# SCH_Genie-V1_2024-07-29.net
KiCad netlist of a schematic drawn in EasyEDA
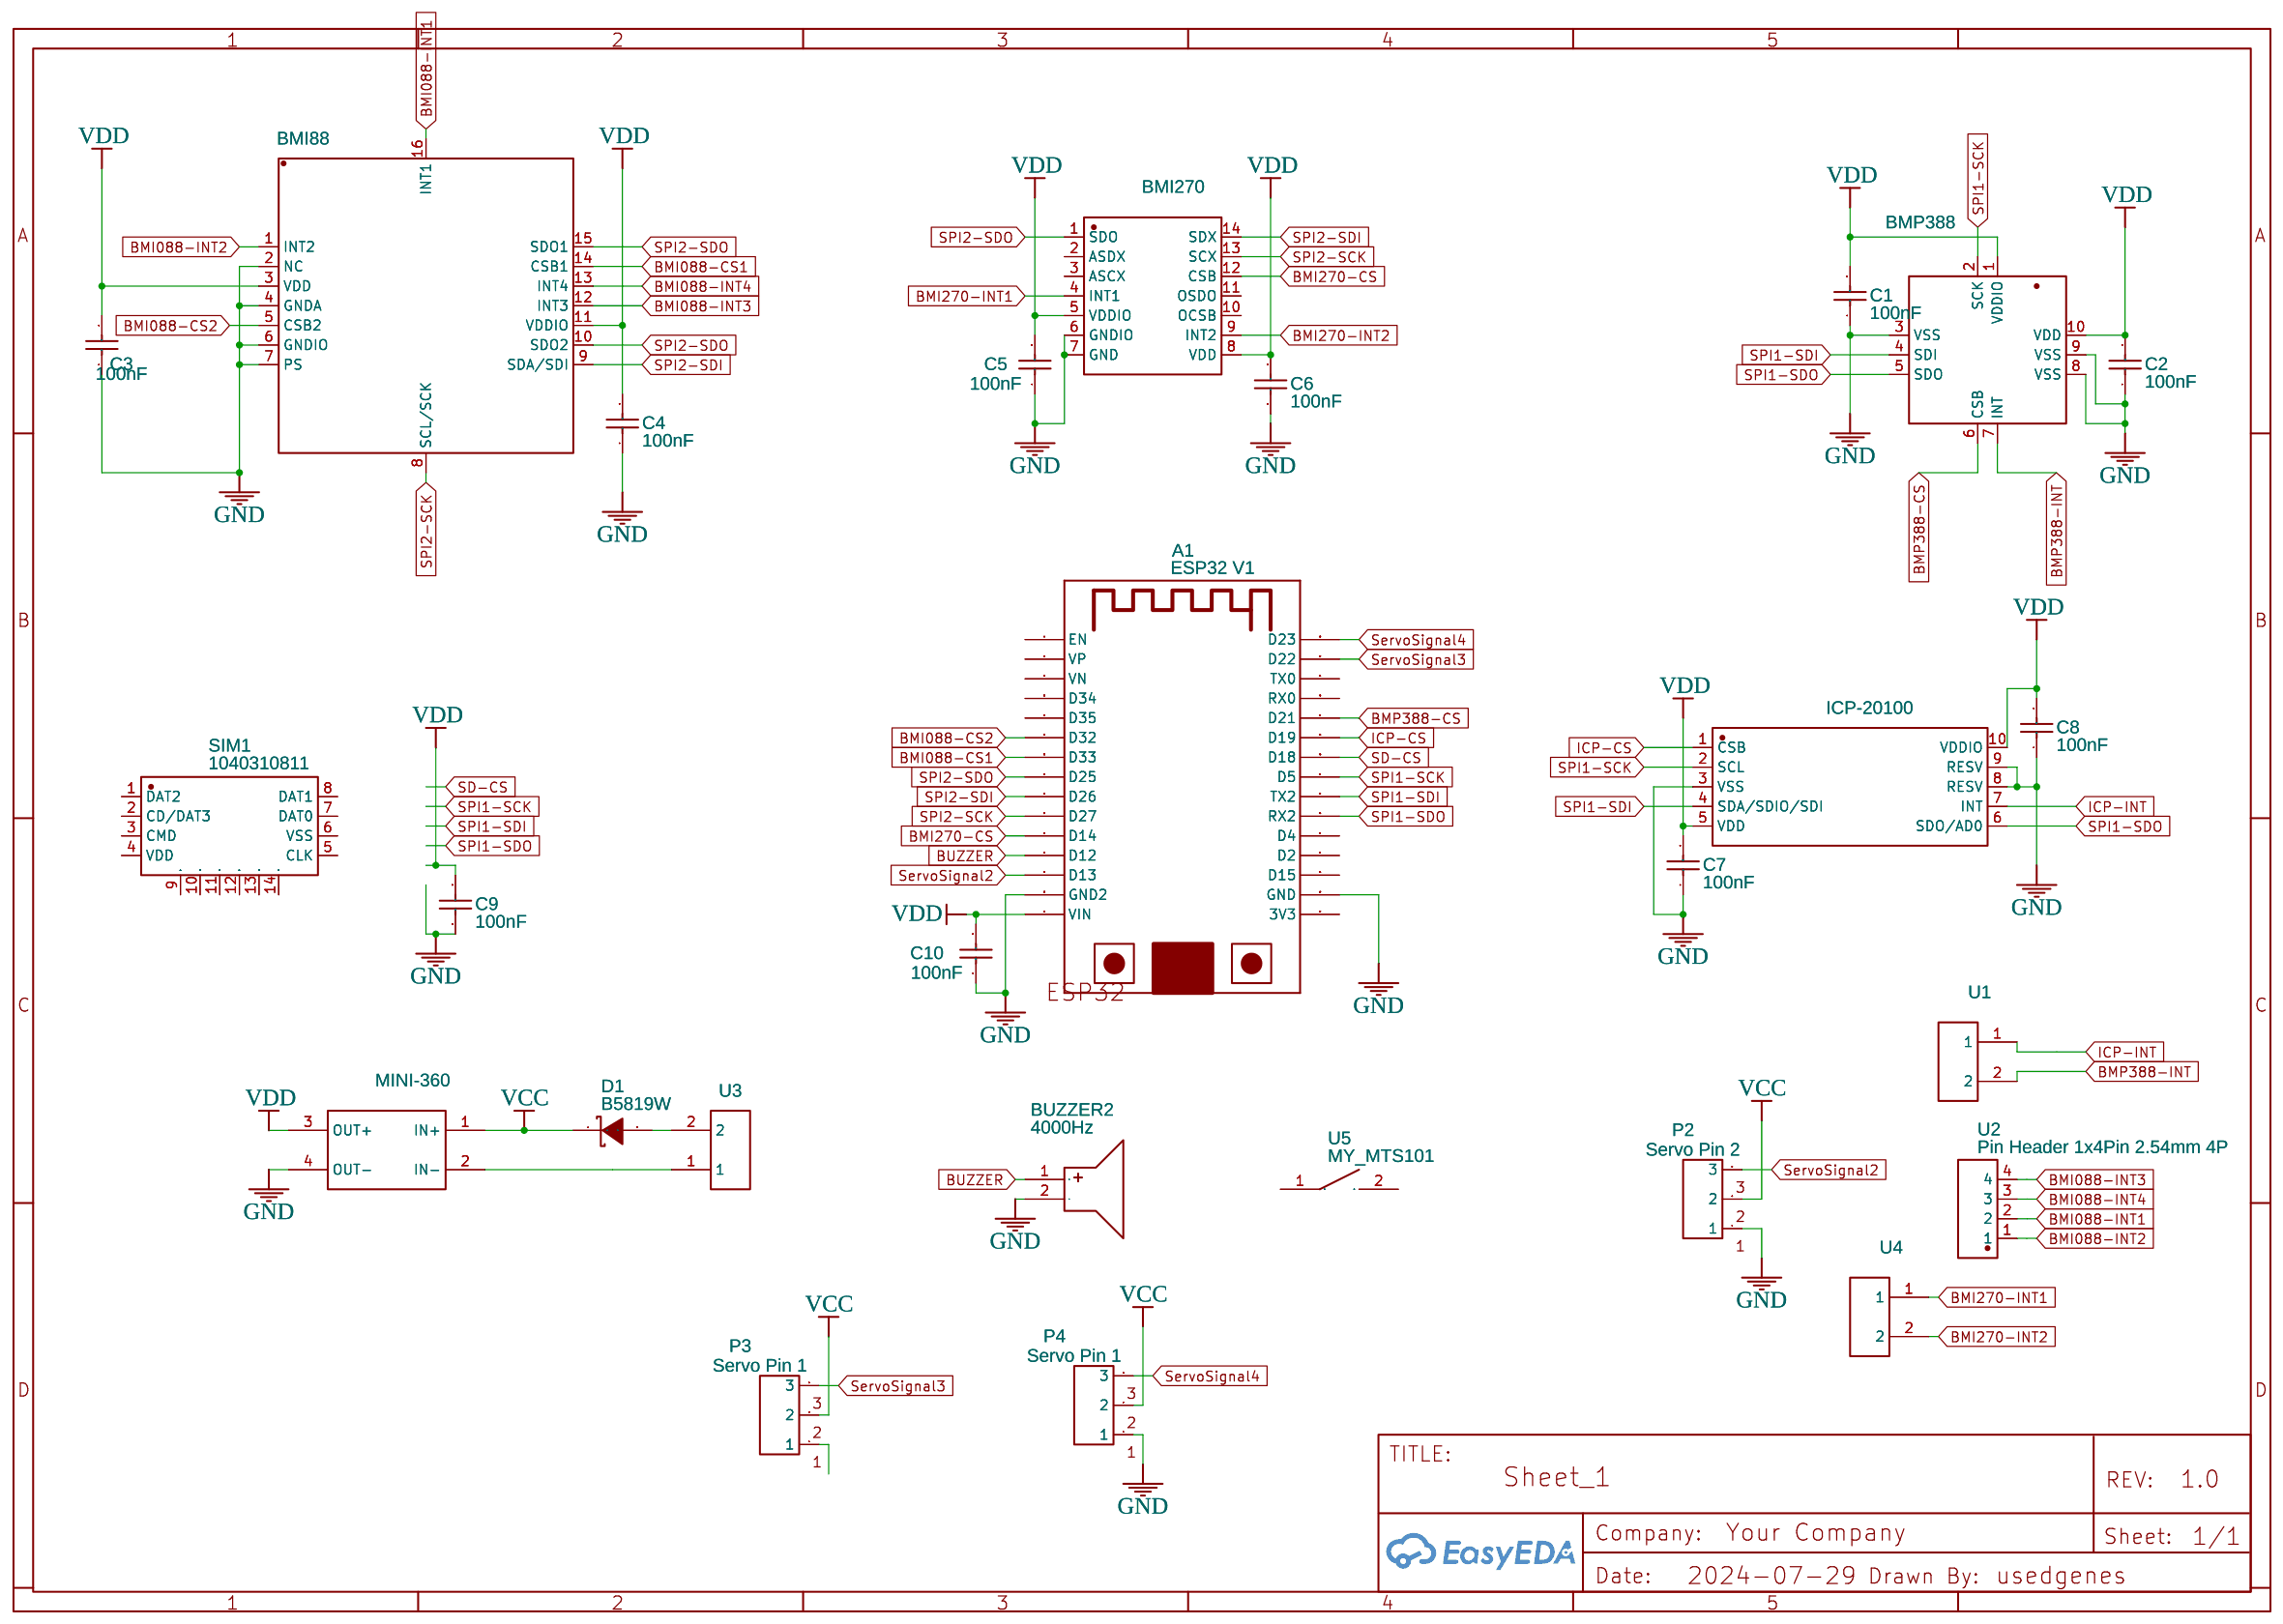
[diagram p0: schematic sheet]

(export (version "E")
  (design (tool "Eeschema 10.0.6"))
  (components
    (comp (ref "A1") (value "ESP32 V1") (libsource (lib "") (part "ESP32-DEVKIT-V1-30PIN")))
    (comp (ref "BMI88")
      (value "BMI088")
      (fields (field (name "Manufacturer") "Bosch(博世)"))
      (libsource (lib "") (part "BMI088"))
    )
    (comp (ref "BMI270")
      (value "BMI270")
      (fields (field (name "Manufacturer") "Bosch(博世)"))
      (libsource (lib "") (part "BMI270"))
    )
    (comp (ref "BMP388")
      (value "BMP388")
      (fields (field (name "Manufacturer") "Bosch(博世)"))
      (libsource (lib "") (part "BMP388"))
    )
    (comp (ref "BUZZER2")
      (value "4000Hz")
      (fields
        (field (name "Manufacturer Part") "SKY-1475-0540-45P7.6")
        (field (name "Manufacturer") "S&S(海旭)")
      )
      (libsource (lib "") (part "SKY-1475-0540-45P7.6"))
    )
    (comp (ref "C1")
      (value "100nF")
      (fields
        (field (name "Manufacturer Part") "CL05B104KO5NNNC")
        (field (name "Manufacturer") "SAMSUNG(三星)")
      )
      (libsource (lib "") (part "CL05B104KO5NNNC"))
    )
    (comp (ref "C2")
      (value "100nF")
      (fields
        (field (name "Manufacturer Part") "CL05B104KO5NNNC")
        (field (name "Manufacturer") "SAMSUNG(三星)")
      )
      (libsource (lib "") (part "CL05B104KO5NNNC"))
    )
    (comp (ref "C3")
      (value "100nF")
      (fields
        (field (name "Manufacturer Part") "CL05B104KO5NNNC")
        (field (name "Manufacturer") "SAMSUNG(三星)")
      )
      (libsource (lib "") (part "CL05B104KO5NNNC"))
    )
    (comp (ref "C4")
      (value "100nF")
      (fields
        (field (name "Manufacturer Part") "CL05B104KO5NNNC")
        (field (name "Manufacturer") "SAMSUNG(三星)")
      )
      (libsource (lib "") (part "CL05B104KO5NNNC"))
    )
    (comp (ref "C5")
      (value "100nF")
      (fields
        (field (name "Manufacturer Part") "CL05B104KO5NNNC")
        (field (name "Manufacturer") "SAMSUNG(三星)")
      )
      (libsource (lib "") (part "CL05B104KO5NNNC"))
    )
    (comp (ref "C6")
      (value "100nF")
      (fields
        (field (name "Manufacturer Part") "CL05B104KO5NNNC")
        (field (name "Manufacturer") "SAMSUNG(三星)")
      )
      (libsource (lib "") (part "CL05B104KO5NNNC"))
    )
    (comp (ref "C7")
      (value "100nF")
      (fields
        (field (name "Manufacturer Part") "CL05B104KO5NNNC")
        (field (name "Manufacturer") "SAMSUNG(三星)")
      )
      (libsource (lib "") (part "CL05B104KO5NNNC"))
    )
    (comp (ref "C8")
      (value "100nF")
      (fields
        (field (name "Manufacturer Part") "CL05B104KO5NNNC")
        (field (name "Manufacturer") "SAMSUNG(三星)")
      )
      (libsource (lib "") (part "CL05B104KO5NNNC"))
    )
    (comp (ref "C9")
      (value "100nF")
      (fields
        (field (name "Manufacturer Part") "CL05B104KO5NNNC")
        (field (name "Manufacturer") "SAMSUNG(三星)")
      )
      (libsource (lib "") (part "CL05B104KO5NNNC"))
    )
    (comp (ref "C10")
      (value "100nF")
      (fields
        (field (name "Manufacturer Part") "CL05B104KO5NNNC")
        (field (name "Manufacturer") "SAMSUNG(三星)")
      )
      (libsource (lib "") (part "CL05B104KO5NNNC"))
    )
    (comp (ref "D1")
      (value "B5819W")
      (fields (field (name "Manufacturer") "MDD(辰达半导体)"))
      (libsource (lib "") (part "B5819W"))
    )
    (comp (ref "ICP-20100")
      (value "ICP-20100")
      (fields (field (name "Manufacturer") "TDK"))
      (libsource (lib "") (part "ICP-20100"))
    )
    (comp (ref "MINI-360") (value "MINI-360") (libsource (lib "") (part "MINI-360")))
    (comp (ref "P2")
      (value "Servo Pin 2")
      (fields
        (field (name "Manufacturer Part") "Female headerHDR1X8-2.54")
        (field (name "Manufacturer") "BOOMELE")
      )
      (libsource (lib "") (part "HEADER PAD 3X RMM COPY"))
    )
    (comp (ref "P3")
      (value "Servo Pin 1")
      (fields
        (field (name "Manufacturer Part") "Female headerHDR1X8-2.54")
        (field (name "Manufacturer") "BOOMELE")
      )
      (libsource (lib "") (part "HEADER PAD 3X RMM COPY"))
    )
    (comp (ref "P4")
      (value "Servo Pin 1")
      (fields
        (field (name "Manufacturer Part") "Female headerHDR1X8-2.54")
        (field (name "Manufacturer") "BOOMELE")
      )
      (libsource (lib "") (part "HEADER PAD 3X RMM COPY"))
    )
    (comp (ref "SIM1")
      (value "1040310811")
      (fields (field (name "Manufacturer") "MOLEX"))
      (libsource (lib "") (part "1040310811"))
    )
    (comp (ref "U1") (value "Power Pins") (libsource (lib "") (part "1X2_1")))
    (comp (ref "U2")
      (value "Pin Header 1x4Pin 2.54mm 4P")
      (libsource (lib "") (part "Pin Header 1x4Pin 2.54mm 4P"))
    )
    (comp (ref "U3") (value "Power Pins") (libsource (lib "") (part "1X2")))
    (comp (ref "U4") (value "Power Pins") (libsource (lib "") (part "1X2_1")))
    (comp (ref "U5")
      (value "MY_MTS101")
      (fields (field (name "Manufacturer") "own"))
      (libsource (lib "") (part "MY_MTS101"))
    )
  )
  (nets
    (net (code "1") (name "BMI088-CS1") (class "Default")
      (node (ref "A1") (pin "D33") (pinfunction "D33_D33") (pintype "unspecified"))
      (node (ref "BMI88") (pin "14") (pinfunction "CSB1_14") (pintype "unspecified"))
    )
    (net (code "2") (name "BMI088-CS2") (class "Default")
      (node (ref "A1") (pin "D32") (pinfunction "D32_D32") (pintype "unspecified"))
      (node (ref "BMI88") (pin "5") (pinfunction "CSB2_5") (pintype "unspecified"))
    )
    (net (code "3") (name "BMI088-INT1") (class "Default")
      (node (ref "BMI88") (pin "16") (pinfunction "INT1_16") (pintype "unspecified"))
      (node (ref "U2") (pin "2") (pinfunction "2_2") (pintype "unspecified"))
    )
    (net (code "4") (name "BMI088-INT2") (class "Default")
      (node (ref "BMI88") (pin "1") (pinfunction "INT2_1") (pintype "unspecified"))
      (node (ref "U2") (pin "1") (pinfunction "1_1") (pintype "unspecified"))
    )
    (net (code "5") (name "BMI088-INT3") (class "Default")
      (node (ref "BMI88") (pin "12") (pinfunction "INT3_12") (pintype "unspecified"))
      (node (ref "U2") (pin "4") (pinfunction "4_4") (pintype "unspecified"))
    )
    (net (code "6") (name "BMI088-INT4") (class "Default")
      (node (ref "BMI88") (pin "13") (pinfunction "INT4_13") (pintype "unspecified"))
      (node (ref "U2") (pin "3") (pinfunction "3_3") (pintype "unspecified"))
    )
    (net (code "7") (name "BMI270-CS") (class "Default")
      (node (ref "A1") (pin "D14") (pinfunction "D14_D14") (pintype "unspecified"))
      (node (ref "BMI270") (pin "12") (pinfunction "CSB_12") (pintype "unspecified"))
    )
    (net (code "8") (name "BMI270-INT1") (class "Default")
      (node (ref "BMI270") (pin "4") (pinfunction "INT1_4") (pintype "unspecified"))
      (node (ref "U4") (pin "1") (pinfunction "1_1") (pintype "unspecified"))
    )
    (net (code "9") (name "BMI270-INT2") (class "Default")
      (node (ref "BMI270") (pin "9") (pinfunction "INT2_9") (pintype "unspecified"))
      (node (ref "U4") (pin "2") (pinfunction "2_2") (pintype "unspecified"))
    )
    (net (code "10") (name "BMP388-CS") (class "Default")
      (node (ref "A1") (pin "D21") (pinfunction "D21_D21") (pintype "unspecified"))
      (node (ref "BMP388") (pin "6") (pinfunction "CSB_6") (pintype "unspecified"))
    )
    (net (code "11") (name "BMP388-INT") (class "Default")
      (node (ref "BMP388") (pin "7") (pinfunction "INT_7") (pintype "unspecified"))
      (node (ref "U1") (pin "2") (pinfunction "2_2") (pintype "unspecified"))
    )
    (net (code "12") (name "BUZZER") (class "Default")
      (node (ref "A1") (pin "D12") (pinfunction "D12_D12") (pintype "unspecified"))
      (node (ref "BUZZER2") (pin "1") (pinfunction "+_1") (pintype "unspecified"))
    )
    (net (code "13") (name "GND") (class "Default")
      (node (ref "A1") (pin "GND") (pinfunction "GND_GND") (pintype "unspecified"))
      (node (ref "A1") (pin "GND2") (pinfunction "GND2_GND2") (pintype "unspecified"))
      (node (ref "BMI270") (pin "6") (pinfunction "GNDIO_6") (pintype "unspecified"))
      (node (ref "BMI270") (pin "7") (pinfunction "GND_7") (pintype "unspecified"))
      (node (ref "BMI88") (pin "2") (pinfunction "NC_2") (pintype "unspecified"))
      (node (ref "BMI88") (pin "4") (pinfunction "GNDA_4") (pintype "unspecified"))
      (node (ref "BMI88") (pin "6") (pinfunction "GNDIO_6") (pintype "unspecified"))
      (node (ref "BMI88") (pin "7") (pinfunction "PS_7") (pintype "unspecified"))
      (node (ref "BMP388") (pin "3") (pinfunction "VSS_3") (pintype "unspecified"))
      (node (ref "BMP388") (pin "8") (pinfunction "VSS_8") (pintype "unspecified"))
      (node (ref "BMP388") (pin "9") (pinfunction "VSS_9") (pintype "unspecified"))
      (node (ref "BUZZER2") (pin "2") (pinfunction "-_2") (pintype "unspecified"))
      (node (ref "C1") (pin "1") (pinfunction "1_1") (pintype "input"))
      (node (ref "C10") (pin "1") (pinfunction "1_1") (pintype "input"))
      (node (ref "C2") (pin "1") (pinfunction "1_1") (pintype "input"))
      (node (ref "C3") (pin "1") (pinfunction "1_1") (pintype "input"))
      (node (ref "C4") (pin "1") (pinfunction "1_1") (pintype "input"))
      (node (ref "C5") (pin "1") (pinfunction "1_1") (pintype "input"))
      (node (ref "C6") (pin "1") (pinfunction "1_1") (pintype "input"))
      (node (ref "C7") (pin "1") (pinfunction "1_1") (pintype "input"))
      (node (ref "C8") (pin "1") (pinfunction "1_1") (pintype "input"))
      (node (ref "C9") (pin "1") (pinfunction "1_1") (pintype "input"))
      (node (ref "ICP-20100") (pin "3") (pinfunction "VSS_3") (pintype "unspecified"))
      (node (ref "ICP-20100") (pin "8") (pinfunction "RESV_8") (pintype "unspecified"))
      (node (ref "ICP-20100") (pin "9") (pinfunction "RESV_9") (pintype "unspecified"))
      (node (ref "MINI-360") (pin "4") (pinfunction "OUT-_4") (pintype "unspecified"))
      (node (ref "P2") (pin "1") (pinfunction "1_1") (pintype "unspecified"))
      (node (ref "P4") (pin "1") (pinfunction "1_1") (pintype "unspecified"))
    )
    (net (code "14") (name "ICP-CS") (class "Default")
      (node (ref "A1") (pin "D19") (pinfunction "D19_D19") (pintype "unspecified"))
      (node (ref "ICP-20100") (pin "1") (pinfunction "CSB_1") (pintype "unspecified"))
    )
    (net (code "15") (name "ICP-INT") (class "Default")
      (node (ref "ICP-20100") (pin "7") (pinfunction "INT_7") (pintype "unspecified"))
      (node (ref "U1") (pin "1") (pinfunction "1_1") (pintype "unspecified"))
    )
    (net (code "16") (name "Net-(D1-A)") (class "Default")
      (node (ref "D1") (pin "2") (pinfunction "A_2") (pintype "unspecified"))
      (node (ref "U3") (pin "2") (pinfunction "2_2") (pintype "unspecified"))
    )
    (net (code "17") (name "Net-(MINI-360-IN-)") (class "Default")
      (node (ref "MINI-360") (pin "2") (pinfunction "IN-_2") (pintype "unspecified"))
      (node (ref "U3") (pin "1") (pinfunction "1_1") (pintype "unspecified"))
    )
    (net (code "18") (name "SD-CS") (class "Default")
      (node (ref "A1") (pin "D18") (pinfunction "D18_D18") (pintype "unspecified"))
    )
    (net (code "19") (name "SPI1-SCK") (class "Default")
      (node (ref "A1") (pin "D5") (pinfunction "D5_D5") (pintype "unspecified"))
      (node (ref "BMP388") (pin "2") (pinfunction "SCK_2") (pintype "unspecified"))
      (node (ref "ICP-20100") (pin "2") (pinfunction "SCL_2") (pintype "unspecified"))
    )
    (net (code "20") (name "SPI1-SDI") (class "Default")
      (node (ref "A1") (pin "TX2") (pinfunction "TX2_TX2") (pintype "unspecified"))
      (node (ref "BMP388") (pin "4") (pinfunction "SDI_4") (pintype "unspecified"))
      (node (ref "ICP-20100") (pin "4") (pinfunction "SDA/SDIO/SDI_4") (pintype "unspecified"))
    )
    (net (code "21") (name "SPI1-SDO") (class "Default")
      (node (ref "A1") (pin "RX2") (pinfunction "RX2_RX2") (pintype "unspecified"))
      (node (ref "BMP388") (pin "5") (pinfunction "SDO_5") (pintype "unspecified"))
      (node (ref "ICP-20100") (pin "6") (pinfunction "SDO/AD0_6") (pintype "unspecified"))
    )
    (net (code "22") (name "SPI2-SCK") (class "Default")
      (node (ref "A1") (pin "D27") (pinfunction "D27_D27") (pintype "unspecified"))
      (node (ref "BMI270") (pin "13") (pinfunction "SCX_13") (pintype "unspecified"))
      (node (ref "BMI88") (pin "8") (pinfunction "SCL/SCK_8") (pintype "unspecified"))
    )
    (net (code "23") (name "SPI2-SDI") (class "Default")
      (node (ref "A1") (pin "D26") (pinfunction "D26_D26") (pintype "unspecified"))
      (node (ref "BMI270") (pin "14") (pinfunction "SDX_14") (pintype "unspecified"))
      (node (ref "BMI88") (pin "9") (pinfunction "SDA/SDI_9") (pintype "unspecified"))
    )
    (net (code "24") (name "SPI2-SDO") (class "Default")
      (node (ref "A1") (pin "D25") (pinfunction "D25_D25") (pintype "unspecified"))
      (node (ref "BMI270") (pin "1") (pinfunction "SDO_1") (pintype "unspecified"))
      (node (ref "BMI88") (pin "10") (pinfunction "SDO2_10") (pintype "unspecified"))
      (node (ref "BMI88") (pin "15") (pinfunction "SDO1_15") (pintype "unspecified"))
    )
    (net (code "25") (name "ServoSignal2") (class "Default")
      (node (ref "A1") (pin "D13") (pinfunction "D13_D13") (pintype "unspecified"))
      (node (ref "P2") (pin "3") (pinfunction "3_3") (pintype "unspecified"))
    )
    (net (code "26") (name "ServoSignal3") (class "Default")
      (node (ref "A1") (pin "D22") (pinfunction "D22_D22") (pintype "unspecified"))
      (node (ref "P3") (pin "3") (pinfunction "3_3") (pintype "unspecified"))
    )
    (net (code "27") (name "ServoSignal4") (class "Default")
      (node (ref "A1") (pin "D23") (pinfunction "D23_D23") (pintype "unspecified"))
      (node (ref "P4") (pin "3") (pinfunction "3_3") (pintype "unspecified"))
    )
    (net (code "28") (name "VCC") (class "Default")
      (node (ref "D1") (pin "1") (pinfunction "K_1") (pintype "unspecified"))
      (node (ref "MINI-360") (pin "1") (pinfunction "IN+_1") (pintype "unspecified"))
      (node (ref "P2") (pin "2") (pinfunction "2_2") (pintype "unspecified"))
      (node (ref "P3") (pin "2") (pinfunction "2_2") (pintype "unspecified"))
      (node (ref "P4") (pin "2") (pinfunction "2_2") (pintype "unspecified"))
    )
    (net (code "29") (name "VDD") (class "Default")
      (node (ref "A1") (pin "VIN") (pinfunction "VIN_VIN") (pintype "unspecified"))
      (node (ref "BMI270") (pin "5") (pinfunction "VDDIO_5") (pintype "unspecified"))
      (node (ref "BMI270") (pin "8") (pinfunction "VDD_8") (pintype "unspecified"))
      (node (ref "BMI88") (pin "11") (pinfunction "VDDIO_11") (pintype "unspecified"))
      (node (ref "BMI88") (pin "3") (pinfunction "VDD_3") (pintype "unspecified"))
      (node (ref "BMP388") (pin "1") (pinfunction "VDDIO_1") (pintype "unspecified"))
      (node (ref "BMP388") (pin "10") (pinfunction "VDD_10") (pintype "unspecified"))
      (node (ref "C1") (pin "2") (pinfunction "2_2") (pintype "input"))
      (node (ref "C10") (pin "2") (pinfunction "2_2") (pintype "input"))
      (node (ref "C2") (pin "2") (pinfunction "2_2") (pintype "input"))
      (node (ref "C3") (pin "2") (pinfunction "2_2") (pintype "input"))
      (node (ref "C4") (pin "2") (pinfunction "2_2") (pintype "input"))
      (node (ref "C5") (pin "2") (pinfunction "2_2") (pintype "input"))
      (node (ref "C6") (pin "2") (pinfunction "2_2") (pintype "input"))
      (node (ref "C7") (pin "2") (pinfunction "2_2") (pintype "input"))
      (node (ref "C8") (pin "2") (pinfunction "2_2") (pintype "input"))
      (node (ref "C9") (pin "2") (pinfunction "2_2") (pintype "input"))
      (node (ref "ICP-20100") (pin "10") (pinfunction "VDDIO_10") (pintype "unspecified"))
      (node (ref "ICP-20100") (pin "5") (pinfunction "VDD_5") (pintype "unspecified"))
      (node (ref "MINI-360") (pin "3") (pinfunction "OUT+_3") (pintype "unspecified"))
    )
    (net (code "30") (name "unconnected-(A1-Pad3V3)") (class "Default")
      (node (ref "A1") (pin "3V3") (pinfunction "3V3_3V3") (pintype "unspecified"))
    )
    (net (code "31") (name "unconnected-(A1-PadD2)") (class "Default")
      (node (ref "A1") (pin "D2") (pinfunction "D2_D2") (pintype "unspecified"))
    )
    (net (code "32") (name "unconnected-(A1-PadD4)") (class "Default")
      (node (ref "A1") (pin "D4") (pinfunction "D4_D4") (pintype "unspecified"))
    )
    (net (code "33") (name "unconnected-(A1-PadD15)") (class "Default")
      (node (ref "A1") (pin "D15") (pinfunction "D15_D15") (pintype "unspecified"))
    )
    (net (code "34") (name "unconnected-(A1-PadD34)") (class "Default")
      (node (ref "A1") (pin "D34") (pinfunction "D34_D34") (pintype "unspecified"))
    )
    (net (code "35") (name "unconnected-(A1-PadD35)") (class "Default")
      (node (ref "A1") (pin "D35") (pinfunction "D35_D35") (pintype "unspecified"))
    )
    (net (code "36") (name "unconnected-(A1-PadEN)") (class "Default")
      (node (ref "A1") (pin "EN") (pinfunction "EN_EN") (pintype "unspecified"))
    )
    (net (code "37") (name "unconnected-(A1-PadRX0)") (class "Default")
      (node (ref "A1") (pin "RX0") (pinfunction "RX0_RX0") (pintype "unspecified"))
    )
    (net (code "38") (name "unconnected-(A1-PadTX0)") (class "Default")
      (node (ref "A1") (pin "TX0") (pinfunction "TX0_TX0") (pintype "unspecified"))
    )
    (net (code "39") (name "unconnected-(A1-PadVN)") (class "Default")
      (node (ref "A1") (pin "VN") (pinfunction "VN_VN") (pintype "unspecified"))
    )
    (net (code "40") (name "unconnected-(A1-PadVP)") (class "Default")
      (node (ref "A1") (pin "VP") (pinfunction "VP_VP") (pintype "unspecified"))
    )
    (net (code "41") (name "unconnected-(BMI270-ASCX-Pad3)") (class "Default")
      (node (ref "BMI270") (pin "3") (pinfunction "ASCX_3") (pintype "unspecified"))
    )
    (net (code "42") (name "unconnected-(BMI270-ASDX-Pad2)") (class "Default")
      (node (ref "BMI270") (pin "2") (pinfunction "ASDX_2") (pintype "unspecified"))
    )
    (net (code "43") (name "unconnected-(BMI270-OCSB-Pad10)") (class "Default")
      (node (ref "BMI270") (pin "10") (pinfunction "OCSB_10") (pintype "unspecified"))
    )
    (net (code "44") (name "unconnected-(BMI270-OSDO-Pad11)") (class "Default")
      (node (ref "BMI270") (pin "11") (pinfunction "OSDO_11") (pintype "unspecified"))
    )
    (net (code "45") (name "unconnected-(P3-Pad1)") (class "Default")
      (node (ref "P3") (pin "1") (pinfunction "1_1") (pintype "unspecified"))
    )
    (net (code "46") (name "unconnected-(SIM1-CD{slash}DAT3-Pad2)") (class "Default")
      (node (ref "SIM1") (pin "2") (pinfunction "CD/DAT3_2") (pintype "unspecified"))
    )
    (net (code "47") (name "unconnected-(SIM1-CLK-Pad5)") (class "Default")
      (node (ref "SIM1") (pin "5") (pinfunction "CLK_5") (pintype "unspecified"))
    )
    (net (code "48") (name "unconnected-(SIM1-CMD-Pad3)") (class "Default")
      (node (ref "SIM1") (pin "3") (pinfunction "CMD_3") (pintype "unspecified"))
    )
    (net (code "49") (name "unconnected-(SIM1-DAT0-Pad7)") (class "Default")
      (node (ref "SIM1") (pin "7") (pinfunction "DAT0_7") (pintype "unspecified"))
    )
    (net (code "50") (name "unconnected-(SIM1-DAT1-Pad8)") (class "Default")
      (node (ref "SIM1") (pin "8") (pinfunction "DAT1_8") (pintype "unspecified"))
    )
    (net (code "51") (name "unconnected-(SIM1-DAT2-Pad1)") (class "Default")
      (node (ref "SIM1") (pin "1") (pinfunction "DAT2_1") (pintype "unspecified"))
    )
    (net (code "52") (name "unconnected-(SIM1-Pad9)") (class "Default")
      (node (ref "SIM1") (pin "9") (pinfunction "9_9") (pintype "unspecified"))
    )
    (net (code "53") (name "unconnected-(SIM1-Pad10)") (class "Default")
      (node (ref "SIM1") (pin "10") (pinfunction "10_10") (pintype "unspecified"))
    )
    (net (code "54") (name "unconnected-(SIM1-Pad11)") (class "Default")
      (node (ref "SIM1") (pin "11") (pinfunction "11_11") (pintype "unspecified"))
    )
    (net (code "55") (name "unconnected-(SIM1-Pad12)") (class "Default")
      (node (ref "SIM1") (pin "12") (pinfunction "12_12") (pintype "unspecified"))
    )
    (net (code "56") (name "unconnected-(SIM1-Pad13)") (class "Default")
      (node (ref "SIM1") (pin "13") (pinfunction "13_13") (pintype "unspecified"))
    )
    (net (code "57") (name "unconnected-(SIM1-Pad14)") (class "Default")
      (node (ref "SIM1") (pin "14") (pinfunction "14_14") (pintype "unspecified"))
    )
    (net (code "58") (name "unconnected-(SIM1-VDD-Pad4)") (class "Default")
      (node (ref "SIM1") (pin "4") (pinfunction "VDD_4") (pintype "unspecified"))
    )
    (net (code "59") (name "unconnected-(SIM1-VSS-Pad6)") (class "Default")
      (node (ref "SIM1") (pin "6") (pinfunction "VSS_6") (pintype "unspecified"))
    )
    (net (code "60") (name "unconnected-(U5-Pad1)") (class "Default")
      (node (ref "U5") (pin "1") (pinfunction "1_1") (pintype "unspecified"))
    )
    (net (code "61") (name "unconnected-(U5-Pad2)") (class "Default")
      (node (ref "U5") (pin "2") (pinfunction "2_2") (pintype "unspecified"))
    )
  )
)
